# aprs_v1.net
KiCad netlist of a schematic drawn in EAGLE
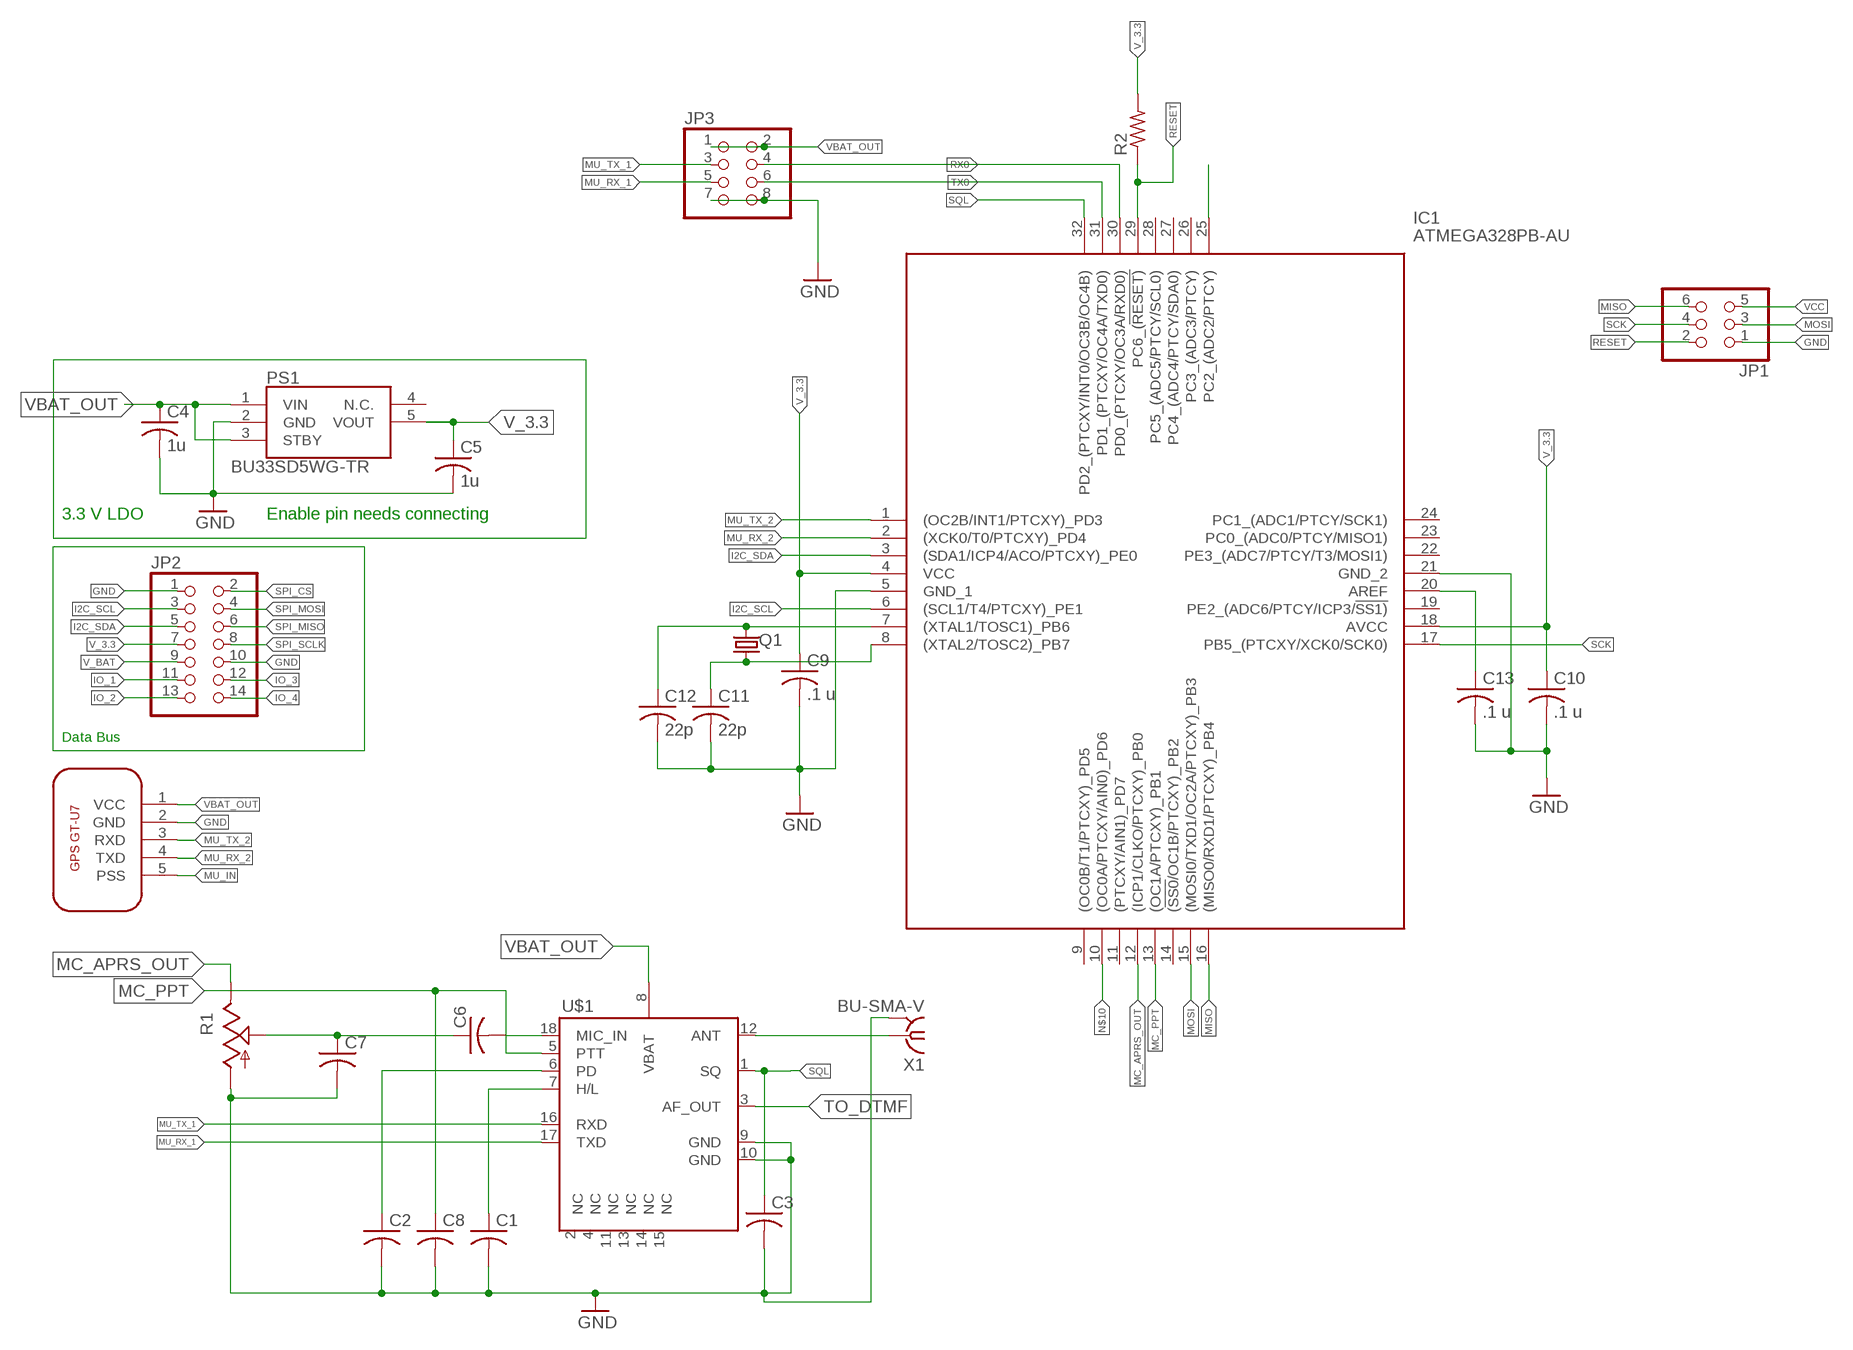
[diagram p0: schematic, sheet 1]

(export (version "E")
  (design (tool "Eeschema 10.0.6"))
  (components
    (comp (ref "C1")
      (value "C-USC0805")
      (footprint "eagle-import:C0805")
      (libsource (lib "eagle-import") (part "C-USC0805"))
    )
    (comp (ref "C2")
      (value "C-USC0805")
      (footprint "eagle-import:C0805")
      (libsource (lib "eagle-import") (part "C-USC0805"))
    )
    (comp (ref "C3")
      (value "C-USC0805")
      (footprint "eagle-import:C0805")
      (libsource (lib "eagle-import") (part "C-USC0805"))
    )
    (comp (ref "C4")
      (value "1u")
      (footprint "eagle-import:C0805")
      (libsource (lib "eagle-import") (part "C-USC0805"))
    )
    (comp (ref "C5")
      (value "1u")
      (footprint "eagle-import:C0805")
      (libsource (lib "eagle-import") (part "C-USC0805"))
    )
    (comp (ref "C6")
      (value "C-USC0805")
      (footprint "eagle-import:C0805")
      (libsource (lib "eagle-import") (part "C-USC0805"))
    )
    (comp (ref "C7")
      (value "C-USC0805")
      (footprint "eagle-import:C0805")
      (libsource (lib "eagle-import") (part "C-USC0805"))
    )
    (comp (ref "C8")
      (value "C-USC0805")
      (footprint "eagle-import:C0805")
      (libsource (lib "eagle-import") (part "C-USC0805"))
    )
    (comp (ref "C9")
      (value ".1 u")
      (footprint "eagle-import:C0805")
      (libsource (lib "eagle-import") (part "C-USC0805"))
    )
    (comp (ref "C10")
      (value ".1 u")
      (footprint "eagle-import:C0805")
      (libsource (lib "eagle-import") (part "C-USC0805"))
    )
    (comp (ref "C11")
      (value "22p")
      (footprint "eagle-import:C0805")
      (libsource (lib "eagle-import") (part "C-USC0805"))
    )
    (comp (ref "C12")
      (value "22p")
      (footprint "eagle-import:C0805")
      (libsource (lib "eagle-import") (part "C-USC0805"))
    )
    (comp (ref "C13")
      (value ".1 u")
      (footprint "eagle-import:C0805")
      (libsource (lib "eagle-import") (part "C-USC0805"))
    )
    (comp (ref "IC1")
      (value "ATMEGA328PB-AU")
      (footprint "eagle-import:QFP80P900X900X120-32N")
      (fields (field (name "MOUSER_PART_NUMBER") "556-ATMEGA328PB-AU"))
      (libsource (lib "eagle-import") (part "ATMEGA328PB-AU"))
    )
    (comp (ref "JP1")
      (value "PINHD-2X3")
      (footprint "eagle-import:2X03")
      (libsource (lib "eagle-import") (part "PINHD-2X3"))
    )
    (comp (ref "JP2")
      (value "PINHD-2X7")
      (footprint "eagle-import:2X07")
      (libsource (lib "eagle-import") (part "PINHD-2X7"))
    )
    (comp (ref "JP3")
      (value "PINHD-2X4")
      (footprint "eagle-import:2X04")
      (libsource (lib "eagle-import") (part "PINHD-2X4"))
    )
    (comp (ref "PS1")
      (value "BU33SD5WG-TR")
      (footprint "eagle-import:SOT95P280X125-5N")
      (fields (field (name "MOUSER_PART_NUMBER") "755-BU33SD5WG-TR"))
      (libsource (lib "eagle-import") (part "BU33SD5WG-TR"))
    )
    (comp (ref "Q1")
      (value "CRYSTALHC49S")
      (footprint "eagle-import:HC49_S")
      (libsource (lib "eagle-import") (part "CRYSTALHC49S"))
    )
    (comp (ref "R1")
      (value "TRIM_US-CA6V")
      (footprint "eagle-import:CA6V")
      (libsource (lib "eagle-import") (part "TRIM_US-CA6V"))
    )
    (comp (ref "R2")
      (value "R-US_M0805")
      (footprint "eagle-import:M0805")
      (libsource (lib "eagle-import") (part "R-US_M0805"))
    )
    (comp (ref "U$1")
      (value "DRA818A")
      (footprint "eagle-import:DRA818A")
      (libsource (lib "eagle-import") (part "DRA818A"))
    )
    (comp (ref "U$2")
      (value "GT-U7")
      (footprint "eagle-import:GPS_AHE")
      (libsource (lib "eagle-import") (part "GT-U7"))
    )
    (comp (ref "X1")
      (value "BU-SMA-V")
      (footprint "eagle-import:BU-SMA-V")
      (libsource (lib "eagle-import") (part "BU-SMA-V"))
    )
  )
  (nets
    (net (code "1") (name "GND") (class "Default")
      (node (ref "C1") (pin "2") (pinfunction "2_2") (pintype "passive"))
      (node (ref "C10") (pin "2") (pinfunction "2_2") (pintype "passive"))
      (node (ref "C11") (pin "2") (pinfunction "2_2") (pintype "passive"))
      (node (ref "C12") (pin "2") (pinfunction "2_2") (pintype "passive"))
      (node (ref "C13") (pin "2") (pinfunction "2_2") (pintype "passive"))
      (node (ref "C2") (pin "2") (pinfunction "2_2") (pintype "passive"))
      (node (ref "C3") (pin "2") (pinfunction "2_2") (pintype "passive"))
      (node (ref "C4") (pin "2") (pinfunction "2_2") (pintype "passive"))
      (node (ref "C5") (pin "2") (pinfunction "2_2") (pintype "passive"))
      (node (ref "C7") (pin "2") (pinfunction "2_2") (pintype "passive"))
      (node (ref "C8") (pin "2") (pinfunction "2_2") (pintype "passive"))
      (node (ref "C9") (pin "2") (pinfunction "2_2") (pintype "passive"))
      (node (ref "IC1") (pin "21") (pinfunction "GND_2_21") (pintype "bidirectional"))
      (node (ref "IC1") (pin "5") (pinfunction "GND_1_5") (pintype "bidirectional"))
      (node (ref "JP1") (pin "1") (pinfunction "1_1") (pintype "passive"))
      (node (ref "JP2") (pin "1") (pinfunction "1_1") (pintype "passive"))
      (node (ref "JP2") (pin "10") (pinfunction "10_10") (pintype "passive"))
      (node (ref "JP3") (pin "7") (pinfunction "7_7") (pintype "passive"))
      (node (ref "JP3") (pin "8") (pinfunction "8_8") (pintype "passive"))
      (node (ref "PS1") (pin "2") (pinfunction "GND_2") (pintype "bidirectional"))
      (node (ref "R1") (pin "A") (pinfunction "A_A") (pintype "passive"))
      (node (ref "U$1") (pin "10") (pinfunction "GND_10") (pintype "bidirectional"))
      (node (ref "U$1") (pin "9") (pinfunction "GND_9") (pintype "bidirectional"))
      (node (ref "U$2") (pin "2") (pinfunction "GND_2") (pintype "bidirectional"))
      (node (ref "X1") (pin "2") (pinfunction "2_2") (pintype "passive"))
      (node (ref "X1") (pin "3") (pinfunction "2_3") (pintype "passive"))
      (node (ref "X1") (pin "4") (pinfunction "2_4") (pintype "passive"))
      (node (ref "X1") (pin "5") (pinfunction "2_5") (pintype "passive"))
    )
    (net (code "2") (name "I2C_SCL") (class "Default")
      (node (ref "IC1") (pin "6") (pinfunction "(SCL1/T4/PTCXY)_PE1_6") (pintype "bidirectional"))
      (node (ref "JP2") (pin "3") (pinfunction "3_3") (pintype "passive"))
    )
    (net (code "3") (name "I2C_SDA") (class "Default")
      (node (ref "IC1") (pin "3") (pinfunction "(SDA1/ICP4/ACO/PTCXY)_PE0_3") (pintype "bidirectional"))
      (node (ref "JP2") (pin "5") (pinfunction "5_5") (pintype "passive"))
    )
    (net (code "4") (name "IO_1") (class "Default")
      (node (ref "JP2") (pin "11") (pinfunction "11_11") (pintype "passive"))
    )
    (net (code "5") (name "IO_2") (class "Default")
      (node (ref "JP2") (pin "13") (pinfunction "13_13") (pintype "passive"))
    )
    (net (code "6") (name "IO_3") (class "Default")
      (node (ref "JP2") (pin "12") (pinfunction "12_12") (pintype "passive"))
    )
    (net (code "7") (name "IO_4") (class "Default")
      (node (ref "JP2") (pin "14") (pinfunction "14_14") (pintype "passive"))
    )
    (net (code "8") (name "MC_APRS_OUT") (class "Default")
      (node (ref "IC1") (pin "12") (pinfunction "(ICP1/CLKO/PTCXY)_PB0_12") (pintype "bidirectional"))
      (node (ref "R1") (pin "E") (pinfunction "E_E") (pintype "passive"))
    )
    (net (code "9") (name "MC_PPT") (class "Default")
      (node (ref "C8") (pin "1") (pinfunction "1_1") (pintype "passive"))
      (node (ref "IC1") (pin "13") (pinfunction "(OC1A/PTCXY)_PB1_13") (pintype "bidirectional"))
      (node (ref "U$1") (pin "5") (pinfunction "PTT_5") (pintype "bidirectional"))
    )
    (net (code "10") (name "MISO") (class "Default")
      (node (ref "IC1") (pin "16") (pinfunction "(MISO0/RXD1/PTCXY)_PB4_16") (pintype "bidirectional"))
      (node (ref "JP1") (pin "6") (pinfunction "6_6") (pintype "passive"))
    )
    (net (code "11") (name "MOSI") (class "Default")
      (node (ref "IC1") (pin "15") (pinfunction "(MOSI0/TXD1/OC2A/PTCXY)_PB3_15") (pintype "bidirectional"))
      (node (ref "JP1") (pin "3") (pinfunction "3_3") (pintype "passive"))
    )
    (net (code "12") (name "MU_IN") (class "Default")
      (node (ref "U$2") (pin "5") (pinfunction "PSS_5") (pintype "bidirectional"))
    )
    (net (code "13") (name "MU_RX_1") (class "Default")
      (node (ref "JP3") (pin "5") (pinfunction "5_5") (pintype "passive"))
      (node (ref "U$1") (pin "17") (pinfunction "TXD_17") (pintype "bidirectional"))
    )
    (net (code "14") (name "MU_RX_2") (class "Default")
      (node (ref "IC1") (pin "2") (pinfunction "(XCK0/T0/PTCXY)_PD4_2") (pintype "bidirectional"))
      (node (ref "U$2") (pin "4") (pinfunction "TXD_4") (pintype "bidirectional"))
    )
    (net (code "15") (name "MU_TX_1") (class "Default")
      (node (ref "JP3") (pin "3") (pinfunction "3_3") (pintype "passive"))
      (node (ref "U$1") (pin "16") (pinfunction "RXD_16") (pintype "bidirectional"))
    )
    (net (code "16") (name "MU_TX_2") (class "Default")
      (node (ref "IC1") (pin "1") (pinfunction "(OC2B/INT1/PTCXY)_PD3_1") (pintype "bidirectional"))
      (node (ref "U$2") (pin "3") (pinfunction "RXD_3") (pintype "bidirectional"))
    )
    (net (code "17") (name "N$10") (class "Default")
      (node (ref "IC1") (pin "10") (pinfunction "(OC0A/PTCXY/AIN0)_PD6_10") (pintype "bidirectional"))
    )
    (net (code "18") (name "Net-(C6-Pad1)") (class "Default")
      (node (ref "C6") (pin "1") (pinfunction "1_1") (pintype "passive"))
      (node (ref "C7") (pin "1") (pinfunction "1_1") (pintype "passive"))
      (node (ref "R1") (pin "S") (pinfunction "S_S") (pintype "passive"))
    )
    (net (code "19") (name "Net-(IC1-(XTAL1{slash}TOSC1)_PB6)") (class "Default")
      (node (ref "C12") (pin "1") (pinfunction "1_1") (pintype "passive"))
      (node (ref "IC1") (pin "7") (pinfunction "(XTAL1/TOSC1)_PB6_7") (pintype "bidirectional"))
      (node (ref "Q1") (pin "2") (pinfunction "2_2") (pintype "passive"))
    )
    (net (code "20") (name "Net-(IC1-(XTAL2{slash}TOSC2)_PB7)") (class "Default")
      (node (ref "C11") (pin "1") (pinfunction "1_1") (pintype "passive"))
      (node (ref "IC1") (pin "8") (pinfunction "(XTAL2/TOSC2)_PB7_8") (pintype "bidirectional"))
      (node (ref "Q1") (pin "1") (pinfunction "1_1") (pintype "passive"))
    )
    (net (code "21") (name "Net-(IC1-AREF)") (class "Default")
      (node (ref "C13") (pin "1") (pinfunction "1_1") (pintype "passive"))
      (node (ref "IC1") (pin "20") (pinfunction "AREF_20") (pintype "bidirectional"))
    )
    (net (code "22") (name "Net-(U$1-ANT)") (class "Default")
      (node (ref "U$1") (pin "12") (pinfunction "ANT_12") (pintype "bidirectional"))
      (node (ref "X1") (pin "1") (pinfunction "1_1") (pintype "passive"))
    )
    (net (code "23") (name "Net-(U$1-H{slash}L)") (class "Default")
      (node (ref "C1") (pin "1") (pinfunction "1_1") (pintype "passive"))
      (node (ref "U$1") (pin "7") (pinfunction "H/L_7") (pintype "bidirectional"))
    )
    (net (code "24") (name "Net-(U$1-MIC_IN)") (class "Default")
      (node (ref "C6") (pin "2") (pinfunction "2_2") (pintype "passive"))
      (node (ref "U$1") (pin "18") (pinfunction "MIC_IN_18") (pintype "bidirectional"))
    )
    (net (code "25") (name "Net-(U$1-PD)") (class "Default")
      (node (ref "C2") (pin "1") (pinfunction "1_1") (pintype "passive"))
      (node (ref "U$1") (pin "6") (pinfunction "PD_6") (pintype "bidirectional"))
    )
    (net (code "26") (name "RESET") (class "Default")
      (node (ref "IC1") (pin "29") (pinfunction "PC6_(~{RESET})_29") (pintype "bidirectional"))
      (node (ref "JP1") (pin "2") (pinfunction "2_2") (pintype "passive"))
      (node (ref "R2") (pin "1") (pinfunction "1_1") (pintype "passive"))
    )
    (net (code "27") (name "RX0") (class "Default")
      (node (ref "IC1") (pin "30") (pinfunction "PD0_(PTCXY/OC3A/RXD0)_30") (pintype "bidirectional"))
      (node (ref "JP3") (pin "4") (pinfunction "4_4") (pintype "passive"))
    )
    (net (code "28") (name "SCK") (class "Default")
      (node (ref "IC1") (pin "17") (pinfunction "PB5_(PTCXY/XCK0/SCK0)_17") (pintype "bidirectional"))
      (node (ref "JP1") (pin "4") (pinfunction "4_4") (pintype "passive"))
    )
    (net (code "29") (name "SPI_CS") (class "Default")
      (node (ref "JP2") (pin "2") (pinfunction "2_2") (pintype "passive"))
    )
    (net (code "30") (name "SPI_MISO") (class "Default")
      (node (ref "JP2") (pin "6") (pinfunction "6_6") (pintype "passive"))
    )
    (net (code "31") (name "SPI_MOSI") (class "Default")
      (node (ref "JP2") (pin "4") (pinfunction "4_4") (pintype "passive"))
    )
    (net (code "32") (name "SPI_SCLK") (class "Default")
      (node (ref "JP2") (pin "8") (pinfunction "8_8") (pintype "passive"))
    )
    (net (code "33") (name "SQL") (class "Default")
      (node (ref "C3") (pin "1") (pinfunction "1_1") (pintype "passive"))
      (node (ref "IC1") (pin "32") (pinfunction "PD2_(PTCXY/INT0/OC3B/OC4B)_32") (pintype "bidirectional"))
      (node (ref "U$1") (pin "1") (pinfunction "SQ_1") (pintype "bidirectional"))
    )
    (net (code "34") (name "TO_DTMF") (class "Default")
      (node (ref "U$1") (pin "3") (pinfunction "AF_OUT_3") (pintype "bidirectional"))
    )
    (net (code "35") (name "TX0") (class "Default")
      (node (ref "IC1") (pin "31") (pinfunction "PD1_(PTCXY/OC4A/TXD0)_31") (pintype "bidirectional"))
      (node (ref "JP3") (pin "6") (pinfunction "6_6") (pintype "passive"))
    )
    (net (code "36") (name "VBAT_OUT") (class "Default")
      (node (ref "C4") (pin "1") (pinfunction "1_1") (pintype "passive"))
      (node (ref "JP3") (pin "1") (pinfunction "1_1") (pintype "passive"))
      (node (ref "JP3") (pin "2") (pinfunction "2_2") (pintype "passive"))
      (node (ref "PS1") (pin "1") (pinfunction "VIN_1") (pintype "bidirectional"))
      (node (ref "PS1") (pin "3") (pinfunction "STBY_3") (pintype "bidirectional"))
      (node (ref "U$1") (pin "8") (pinfunction "VBAT_8") (pintype "bidirectional"))
      (node (ref "U$2") (pin "1") (pinfunction "VCC_1") (pintype "bidirectional"))
    )
    (net (code "37") (name "VCC") (class "Default")
      (node (ref "JP1") (pin "5") (pinfunction "5_5") (pintype "passive"))
    )
    (net (code "38") (name "V_3.3") (class "Default")
      (node (ref "C10") (pin "1") (pinfunction "1_1") (pintype "passive"))
      (node (ref "C5") (pin "1") (pinfunction "1_1") (pintype "passive"))
      (node (ref "C9") (pin "1") (pinfunction "1_1") (pintype "passive"))
      (node (ref "IC1") (pin "18") (pinfunction "AVCC_18") (pintype "bidirectional"))
      (node (ref "IC1") (pin "4") (pinfunction "VCC_4") (pintype "bidirectional"))
      (node (ref "JP2") (pin "7") (pinfunction "7_7") (pintype "passive"))
      (node (ref "PS1") (pin "5") (pinfunction "VOUT_5") (pintype "bidirectional"))
      (node (ref "R2") (pin "2") (pinfunction "2_2") (pintype "passive"))
    )
    (net (code "39") (name "V_BAT") (class "Default")
      (node (ref "JP2") (pin "9") (pinfunction "9_9") (pintype "passive"))
    )
    (net (code "40") (name "unconnected-(IC1-(OC0B{slash}T1{slash}PTCXY)_PD5-Pad9)") (class "Default")
      (node (ref "IC1") (pin "9") (pinfunction "(OC0B/T1/PTCXY)_PD5_9") (pintype "bidirectional"))
    )
    (net (code "41") (name "unconnected-(IC1-(PTCXY{slash}AIN1)_PD7-Pad11)") (class "Default")
      (node (ref "IC1") (pin "11") (pinfunction "(PTCXY/AIN1)_PD7_11") (pintype "bidirectional"))
    )
    (net (code "42") (name "unconnected-(IC1-(~{SS0}{slash}OC1B{slash}PTCXY)_PB2-Pad14)") (class "Default")
      (node (ref "IC1") (pin "14") (pinfunction "(~{SS0}/OC1B/PTCXY)_PB2_14") (pintype "bidirectional"))
    )
    (net (code "43") (name "unconnected-(IC1-PC0_(ADC0{slash}PTCY{slash}MISO1)-Pad23)") (class "Default")
      (node (ref "IC1") (pin "23") (pinfunction "PC0_(ADC0/PTCY/MISO1)_23") (pintype "bidirectional"))
    )
    (net (code "44") (name "unconnected-(IC1-PC1_(ADC1{slash}PTCY{slash}SCK1)-Pad24)") (class "Default")
      (node (ref "IC1") (pin "24") (pinfunction "PC1_(ADC1/PTCY/SCK1)_24") (pintype "bidirectional"))
    )
    (net (code "45") (name "unconnected-(IC1-PC2_(ADC2{slash}PTCY)-Pad25)") (class "Default")
      (node (ref "IC1") (pin "25") (pinfunction "PC2_(ADC2/PTCY)_25") (pintype "bidirectional"))
    )
    (net (code "46") (name "unconnected-(IC1-PC3_(ADC3{slash}PTCY)-Pad26)") (class "Default")
      (node (ref "IC1") (pin "26") (pinfunction "PC3_(ADC3/PTCY)_26") (pintype "bidirectional"))
    )
    (net (code "47") (name "unconnected-(IC1-PC4_(ADC4{slash}PTCY{slash}SDA0)-Pad27)") (class "Default")
      (node (ref "IC1") (pin "27") (pinfunction "PC4_(ADC4/PTCY/SDA0)_27") (pintype "bidirectional"))
    )
    (net (code "48") (name "unconnected-(IC1-PC5_(ADC5{slash}PTCY{slash}SCL0)-Pad28)") (class "Default")
      (node (ref "IC1") (pin "28") (pinfunction "PC5_(ADC5/PTCY/SCL0)_28") (pintype "bidirectional"))
    )
    (net (code "49") (name "unconnected-(IC1-PE2_(ADC6{slash}PTCY{slash}ICP3{slash}~{SS1})-Pad19)") (class "Default")
      (node (ref "IC1") (pin "19") (pinfunction "PE2_(ADC6/PTCY/ICP3/~{SS1})_19") (pintype "bidirectional"))
    )
    (net (code "50") (name "unconnected-(IC1-PE3_(ADC7{slash}PTCY{slash}T3{slash}MOSI1)-Pad22)") (class "Default")
      (node (ref "IC1") (pin "22") (pinfunction "PE3_(ADC7/PTCY/T3/MOSI1)_22") (pintype "bidirectional"))
    )
    (net (code "51") (name "unconnected-(PS1-N.C.-Pad4)") (class "Default")
      (node (ref "PS1") (pin "4") (pinfunction "N.C._4") (pintype "no_connect"))
    )
    (net (code "52") (name "unconnected-(U$1-NC-Pad2)") (class "Default")
      (node (ref "U$1") (pin "2") (pinfunction "NC_2") (pintype "bidirectional"))
    )
    (net (code "53") (name "unconnected-(U$1-NC-Pad4)") (class "Default")
      (node (ref "U$1") (pin "4") (pinfunction "NC_4") (pintype "bidirectional"))
    )
    (net (code "54") (name "unconnected-(U$1-NC-Pad11)") (class "Default")
      (node (ref "U$1") (pin "11") (pinfunction "NC_11") (pintype "bidirectional"))
    )
    (net (code "55") (name "unconnected-(U$1-NC-Pad13)") (class "Default")
      (node (ref "U$1") (pin "13") (pinfunction "NC_13") (pintype "bidirectional"))
    )
    (net (code "56") (name "unconnected-(U$1-NC-Pad14)") (class "Default")
      (node (ref "U$1") (pin "14") (pinfunction "NC_14") (pintype "bidirectional"))
    )
    (net (code "57") (name "unconnected-(U$1-NC-Pad15)") (class "Default")
      (node (ref "U$1") (pin "15") (pinfunction "NC_15") (pintype "bidirectional"))
    )
  )
)
